# Current_Sense.net
KiCad netlist of a schematic drawn in Altium Designer
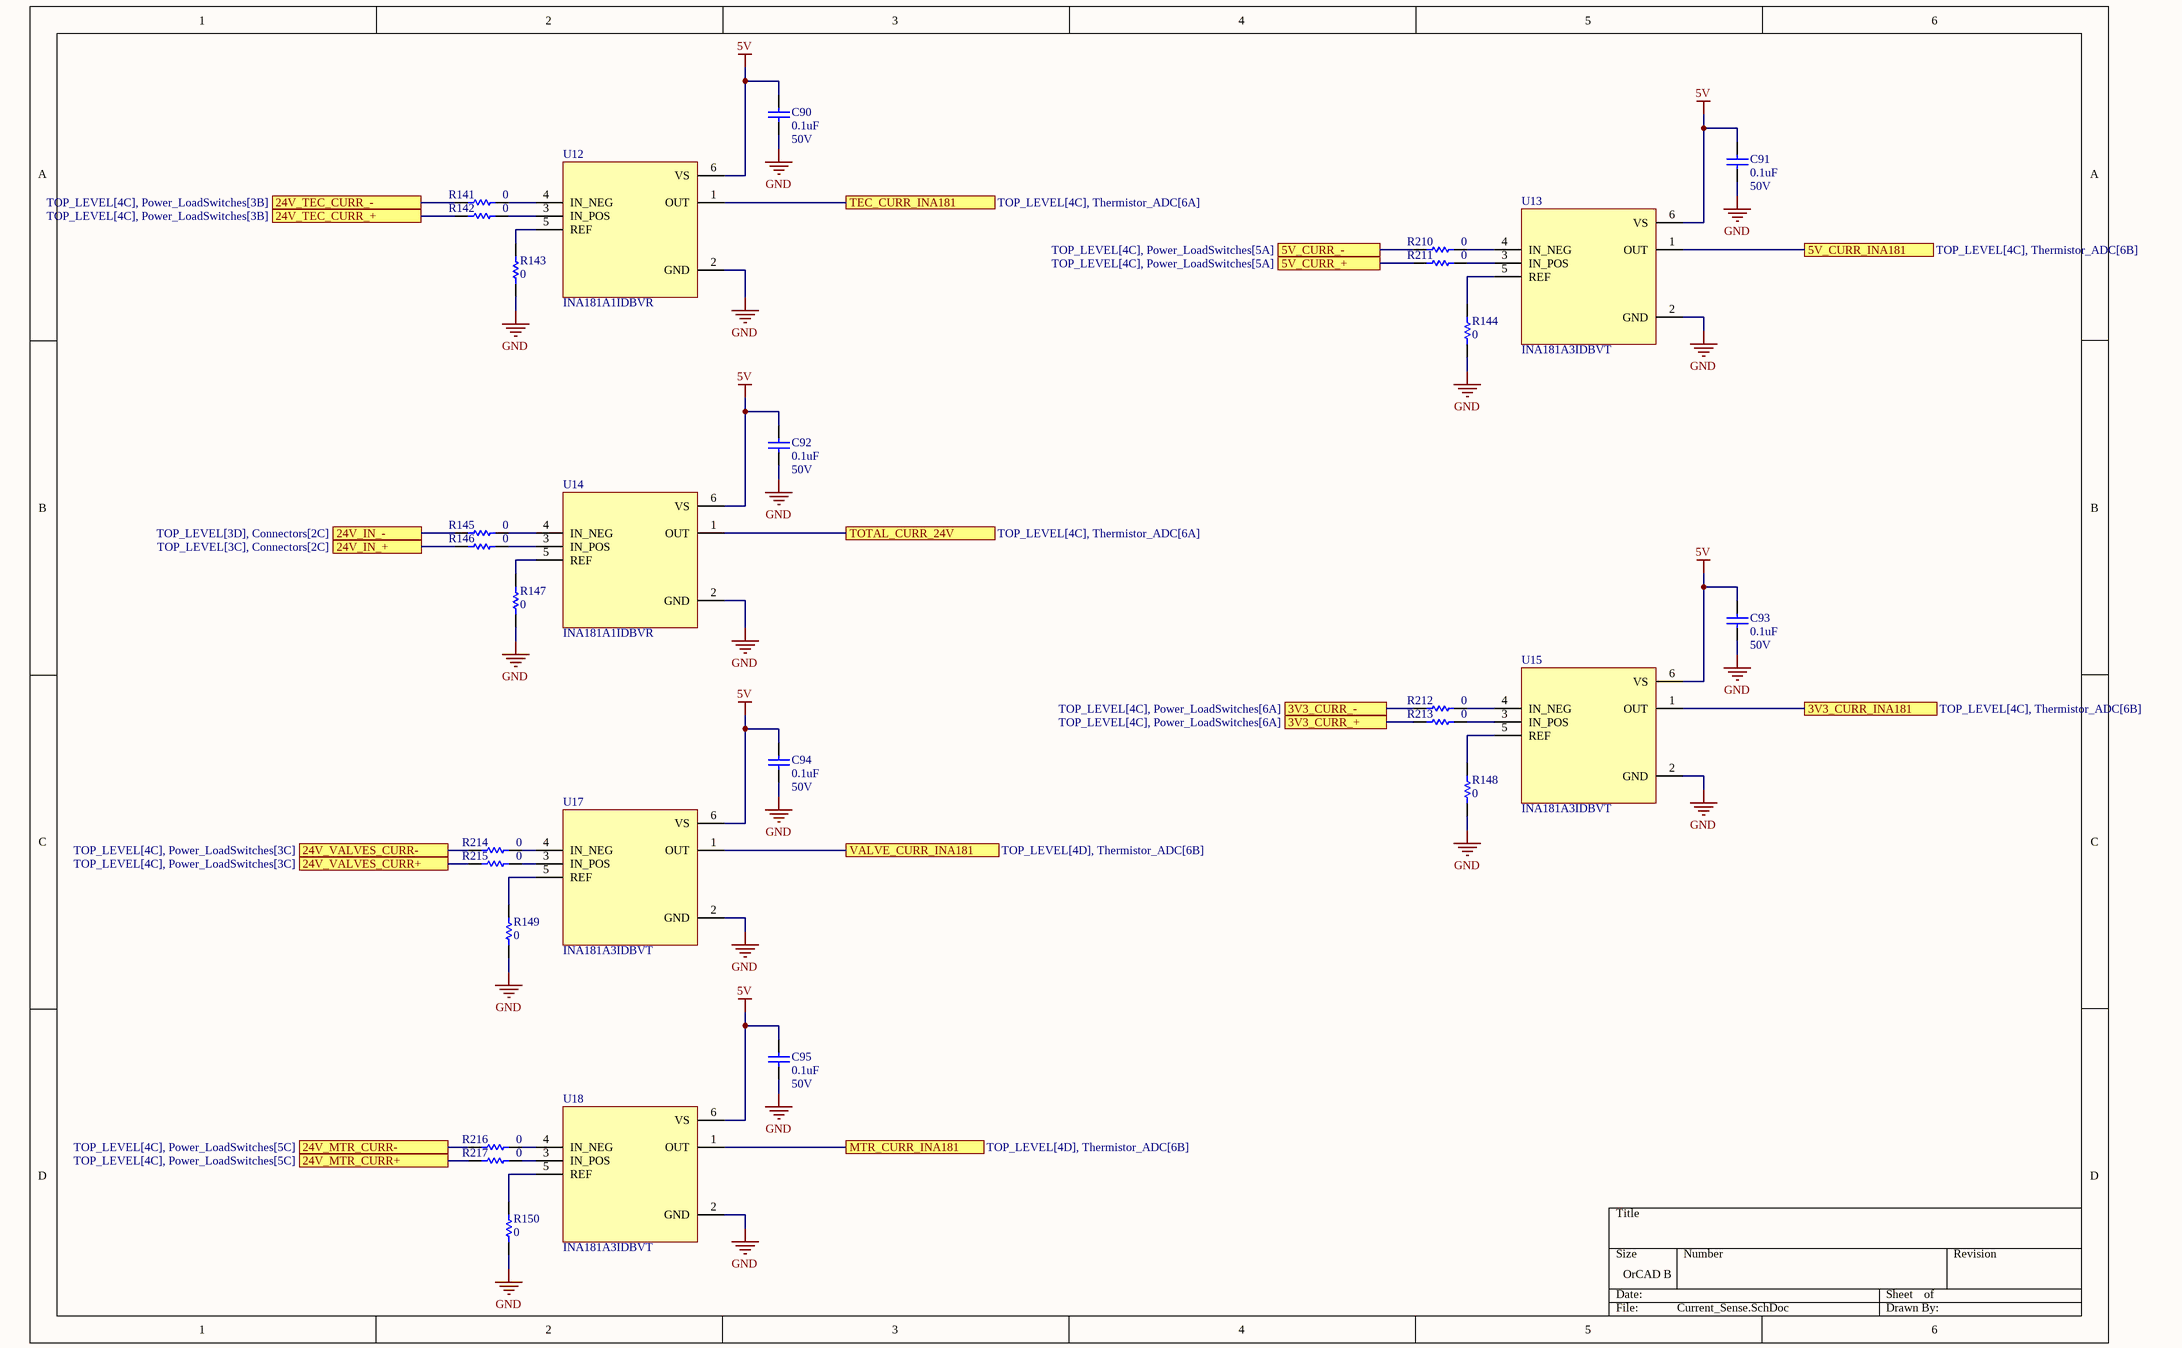
[diagram p0: Current_Sense.SchDoc]

(export (version "E")
  (design (tool "Eeschema 10.0.6"))
  (components
    (comp (ref "C90")
      (value "0.1uF")
      (footprint "DEFAULT_CAPACITOR_0805")
      (description "CAP CER 0.1UF 50V X7R 0805")
      (fields
        (field (name "MANUFACTURER") "Cal-Chip Electronics, Inc.")
        (field (name "RATING") "50V")
        (field (name "Comment") "KGM21NR71H104KT")
      )
      (libsource (lib "Avery Altium Llibrary") (part "KGM21NR71H104KT"))
    )
    (comp (ref "C91")
      (value "0.1uF")
      (footprint "DEFAULT_CAPACITOR_0805")
      (description "CAP CER 0.1UF 50V X7R 0805")
      (fields
        (field (name "MANUFACTURER") "Cal-Chip Electronics, Inc.")
        (field (name "RATING") "50V")
        (field (name "Comment") "KGM21NR71H104KT")
      )
      (libsource (lib "Avery Altium Llibrary") (part "KGM21NR71H104KT"))
    )
    (comp (ref "C92")
      (value "0.1uF")
      (footprint "DEFAULT_CAPACITOR_0805")
      (description "CAP CER 0.1UF 50V X7R 0805")
      (fields
        (field (name "MANUFACTURER") "Cal-Chip Electronics, Inc.")
        (field (name "RATING") "50V")
        (field (name "Comment") "KGM21NR71H104KT")
      )
      (libsource (lib "Avery Altium Llibrary") (part "KGM21NR71H104KT"))
    )
    (comp (ref "C93")
      (value "0.1uF")
      (footprint "DEFAULT_CAPACITOR_0805")
      (description "CAP CER 0.1UF 50V X7R 0805")
      (fields
        (field (name "MANUFACTURER") "Cal-Chip Electronics, Inc.")
        (field (name "RATING") "50V")
        (field (name "Comment") "KGM21NR71H104KT")
      )
      (libsource (lib "Avery Altium Llibrary") (part "KGM21NR71H104KT"))
    )
    (comp (ref "C94")
      (value "0.1uF")
      (footprint "DEFAULT_CAPACITOR_0805")
      (description "CAP CER 0.1UF 50V X7R 0805")
      (fields
        (field (name "MANUFACTURER") "Cal-Chip Electronics, Inc.")
        (field (name "RATING") "50V")
        (field (name "Comment") "KGM21NR71H104KT")
      )
      (libsource (lib "Avery Altium Llibrary") (part "KGM21NR71H104KT"))
    )
    (comp (ref "C95")
      (value "0.1uF")
      (footprint "DEFAULT_CAPACITOR_0805")
      (description "CAP CER 0.1UF 50V X7R 0805")
      (fields
        (field (name "MANUFACTURER") "Cal-Chip Electronics, Inc.")
        (field (name "RATING") "50V")
        (field (name "Comment") "KGM21NR71H104KT")
      )
      (libsource (lib "Avery Altium Llibrary") (part "KGM21NR71H104KT"))
    )
    (comp (ref "R141")
      (value "0")
      (footprint "DEFAULT_RESISTOR_0805")
      (description "RES 0 OHM JUMPER 1/8W 0805")
      (fields (field (name "POWER") "1/8W") (field (name "Comment") "RC0805JR-070RL"))
      (libsource (lib "Avery Altium Llibrary") (part "RC0805JR-070RL"))
    )
    (comp (ref "R142")
      (value "0")
      (footprint "DEFAULT_RESISTOR_0805")
      (description "RES 0 OHM JUMPER 1/8W 0805")
      (fields (field (name "POWER") "1/8W") (field (name "Comment") "RC0805JR-070RL"))
      (libsource (lib "Avery Altium Llibrary") (part "RC0805JR-070RL"))
    )
    (comp (ref "R143")
      (value "0")
      (footprint "DEFAULT_RESISTOR_0805")
      (description "RES 0 OHM JUMPER 1/8W 0805")
      (fields (field (name "POWER") "1/8W") (field (name "Comment") "RC0805JR-070RL"))
      (libsource (lib "Avery Altium Llibrary") (part "RC0805JR-070RL"))
    )
    (comp (ref "R144")
      (value "0")
      (footprint "DEFAULT_RESISTOR_0805")
      (description "RES 0 OHM JUMPER 1/8W 0805")
      (fields (field (name "POWER") "1/8W") (field (name "Comment") "RC0805JR-070RL"))
      (libsource (lib "Avery Altium Llibrary") (part "RC0805JR-070RL"))
    )
    (comp (ref "R145")
      (value "0")
      (footprint "DEFAULT_RESISTOR_0805")
      (description "RES 0 OHM JUMPER 1/8W 0805")
      (fields (field (name "POWER") "1/8W") (field (name "Comment") "RC0805JR-070RL"))
      (libsource (lib "Avery Altium Llibrary") (part "RC0805JR-070RL"))
    )
    (comp (ref "R146")
      (value "0")
      (footprint "DEFAULT_RESISTOR_0805")
      (description "RES 0 OHM JUMPER 1/8W 0805")
      (fields (field (name "POWER") "1/8W") (field (name "Comment") "RC0805JR-070RL"))
      (libsource (lib "Avery Altium Llibrary") (part "RC0805JR-070RL"))
    )
    (comp (ref "R147")
      (value "0")
      (footprint "DEFAULT_RESISTOR_0805")
      (description "RES 0 OHM JUMPER 1/8W 0805")
      (fields (field (name "POWER") "1/8W") (field (name "Comment") "RC0805JR-070RL"))
      (libsource (lib "Avery Altium Llibrary") (part "RC0805JR-070RL"))
    )
    (comp (ref "R148")
      (value "0")
      (footprint "DEFAULT_RESISTOR_0805")
      (description "RES 0 OHM JUMPER 1/8W 0805")
      (fields (field (name "POWER") "1/8W") (field (name "Comment") "RC0805JR-070RL"))
      (libsource (lib "Avery Altium Llibrary") (part "RC0805JR-070RL"))
    )
    (comp (ref "R149")
      (value "0")
      (footprint "DEFAULT_RESISTOR_0805")
      (description "RES 0 OHM JUMPER 1/8W 0805")
      (fields (field (name "POWER") "1/8W") (field (name "Comment") "RC0805JR-070RL"))
      (libsource (lib "Avery Altium Llibrary") (part "RC0805JR-070RL"))
    )
    (comp (ref "R150")
      (value "0")
      (footprint "DEFAULT_RESISTOR_0805")
      (description "RES 0 OHM JUMPER 1/8W 0805")
      (fields (field (name "POWER") "1/8W") (field (name "Comment") "RC0805JR-070RL"))
      (libsource (lib "Avery Altium Llibrary") (part "RC0805JR-070RL"))
    )
    (comp (ref "R210")
      (value "0")
      (footprint "DEFAULT_RESISTOR_0805")
      (description "RES 0 OHM JUMPER 1/8W 0805")
      (fields (field (name "POWER") "1/8W") (field (name "Comment") "RC0805JR-070RL"))
      (libsource (lib "Avery Altium Llibrary") (part "RC0805JR-070RL"))
    )
    (comp (ref "R211")
      (value "0")
      (footprint "DEFAULT_RESISTOR_0805")
      (description "RES 0 OHM JUMPER 1/8W 0805")
      (fields (field (name "POWER") "1/8W") (field (name "Comment") "RC0805JR-070RL"))
      (libsource (lib "Avery Altium Llibrary") (part "RC0805JR-070RL"))
    )
    (comp (ref "R212")
      (value "0")
      (footprint "DEFAULT_RESISTOR_0805")
      (description "RES 0 OHM JUMPER 1/8W 0805")
      (fields (field (name "POWER") "1/8W") (field (name "Comment") "RC0805JR-070RL"))
      (libsource (lib "Avery Altium Llibrary") (part "RC0805JR-070RL"))
    )
    (comp (ref "R213")
      (value "0")
      (footprint "DEFAULT_RESISTOR_0805")
      (description "RES 0 OHM JUMPER 1/8W 0805")
      (fields (field (name "POWER") "1/8W") (field (name "Comment") "RC0805JR-070RL"))
      (libsource (lib "Avery Altium Llibrary") (part "RC0805JR-070RL"))
    )
    (comp (ref "R214")
      (value "0")
      (footprint "DEFAULT_RESISTOR_0805")
      (description "RES 0 OHM JUMPER 1/8W 0805")
      (fields (field (name "POWER") "1/8W") (field (name "Comment") "RC0805JR-070RL"))
      (libsource (lib "Avery Altium Llibrary") (part "RC0805JR-070RL"))
    )
    (comp (ref "R215")
      (value "0")
      (footprint "DEFAULT_RESISTOR_0805")
      (description "RES 0 OHM JUMPER 1/8W 0805")
      (fields (field (name "POWER") "1/8W") (field (name "Comment") "RC0805JR-070RL"))
      (libsource (lib "Avery Altium Llibrary") (part "RC0805JR-070RL"))
    )
    (comp (ref "R216")
      (value "0")
      (footprint "DEFAULT_RESISTOR_0805")
      (description "RES 0 OHM JUMPER 1/8W 0805")
      (fields (field (name "POWER") "1/8W") (field (name "Comment") "RC0805JR-070RL"))
      (libsource (lib "Avery Altium Llibrary") (part "RC0805JR-070RL"))
    )
    (comp (ref "R217")
      (value "0")
      (footprint "DEFAULT_RESISTOR_0805")
      (description "RES 0 OHM JUMPER 1/8W 0805")
      (fields (field (name "POWER") "1/8W") (field (name "Comment") "RC0805JR-070RL"))
      (libsource (lib "Avery Altium Llibrary") (part "RC0805JR-070RL"))
    )
    (comp (ref "U12")
      (value "INA181A1IDBVR")
      (footprint "INA181A1IDBVR")
      (description "IC CURR SENSE 1 CIRCUIT SOT23-6")
      (fields (field (name "MF") "Texas Instruments"))
      (libsource (lib "Avery Schem Library") (part "INA181A1IDBVR"))
    )
    (comp (ref "U13")
      (value "INA181A3IDBVT")
      (footprint "INA181A1IDBVR")
      (description "IC CURR SENSE 1 CIRCUIT SOT23-6")
      (fields (field (name "MF") "Texas Instruments") (field (name "MP") "INA181A1IDBVR"))
      (libsource (lib "Avery Schem Library") (part "INA181A3IDBVT"))
    )
    (comp (ref "U14")
      (value "INA181A1IDBVR")
      (footprint "INA181A1IDBVR")
      (description "IC CURR SENSE 1 CIRCUIT SOT23-6")
      (fields (field (name "MF") "Texas Instruments"))
      (libsource (lib "Avery Schem Library") (part "INA181A1IDBVR"))
    )
    (comp (ref "U15")
      (value "INA181A3IDBVT")
      (footprint "INA181A1IDBVR")
      (description "IC CURR SENSE 1 CIRCUIT SOT23-6")
      (fields (field (name "MF") "Texas Instruments") (field (name "MP") "INA181A1IDBVR"))
      (libsource (lib "Avery Schem Library") (part "INA181A3IDBVT"))
    )
    (comp (ref "U17")
      (value "INA181A3IDBVT")
      (footprint "INA181A1IDBVR")
      (description "IC CURR SENSE 1 CIRCUIT SOT23-6")
      (fields (field (name "MF") "Texas Instruments") (field (name "MP") "INA181A1IDBVR"))
      (libsource (lib "Avery Schem Library") (part "INA181A3IDBVT"))
    )
    (comp (ref "U18")
      (value "INA181A3IDBVT")
      (footprint "INA181A1IDBVR")
      (description "IC CURR SENSE 1 CIRCUIT SOT23-6")
      (fields (field (name "MF") "Texas Instruments") (field (name "MP") "INA181A1IDBVR"))
      (libsource (lib "Avery Schem Library") (part "INA181A3IDBVT"))
    )
  )
  (nets
    (net (code "1") (name "/3V3_CURR_+") (class "Default")
      (node (ref "R213") (pin "2") (pinfunction "2_2") (pintype "passive"))
    )
    (net (code "2") (name "/3V3_CURR_-") (class "Default")
      (node (ref "R212") (pin "2") (pinfunction "2_2") (pintype "passive"))
    )
    (net (code "3") (name "/3V3_CURR_INA181") (class "Default")
      (node (ref "U15") (pin "1") (pinfunction "OUT_1") (pintype "passive"))
    )
    (net (code "4") (name "/5V_CURR_+") (class "Default")
      (node (ref "R211") (pin "2") (pinfunction "2_2") (pintype "passive"))
    )
    (net (code "5") (name "/5V_CURR_-") (class "Default")
      (node (ref "R210") (pin "2") (pinfunction "2_2") (pintype "passive"))
    )
    (net (code "6") (name "/5V_CURR_INA181") (class "Default")
      (node (ref "U13") (pin "1") (pinfunction "OUT_1") (pintype "passive"))
    )
    (net (code "7") (name "/24V_IN_+") (class "Default")
      (node (ref "R146") (pin "2") (pinfunction "2_2") (pintype "passive"))
    )
    (net (code "8") (name "/24V_IN_-") (class "Default")
      (node (ref "R145") (pin "2") (pinfunction "2_2") (pintype "passive"))
    )
    (net (code "9") (name "/24V_MTR_CURR+") (class "Default")
      (node (ref "R217") (pin "2") (pinfunction "2_2") (pintype "passive"))
    )
    (net (code "10") (name "/24V_MTR_CURR-") (class "Default")
      (node (ref "R216") (pin "2") (pinfunction "2_2") (pintype "passive"))
    )
    (net (code "11") (name "/24V_TEC_CURR_+") (class "Default")
      (node (ref "R142") (pin "2") (pinfunction "2_2") (pintype "passive"))
    )
    (net (code "12") (name "/24V_TEC_CURR_-") (class "Default")
      (node (ref "R141") (pin "2") (pinfunction "2_2") (pintype "passive"))
    )
    (net (code "13") (name "/24V_VALVES_CURR+") (class "Default")
      (node (ref "R215") (pin "2") (pinfunction "2_2") (pintype "passive"))
    )
    (net (code "14") (name "/24V_VALVES_CURR-") (class "Default")
      (node (ref "R214") (pin "2") (pinfunction "2_2") (pintype "passive"))
    )
    (net (code "15") (name "/MTR_CURR_INA181") (class "Default")
      (node (ref "U18") (pin "1") (pinfunction "OUT_1") (pintype "passive"))
    )
    (net (code "16") (name "/TEC_CURR_INA181") (class "Default")
      (node (ref "U12") (pin "1") (pinfunction "OUT_1") (pintype "passive"))
    )
    (net (code "17") (name "/TOTAL_CURR_24V") (class "Default")
      (node (ref "U14") (pin "1") (pinfunction "OUT_1") (pintype "passive"))
    )
    (net (code "18") (name "/VALVE_CURR_INA181") (class "Default")
      (node (ref "U17") (pin "1") (pinfunction "OUT_1") (pintype "passive"))
    )
    (net (code "19") (name "5V") (class "Default")
      (node (ref "C90") (pin "2") (pinfunction "2_2") (pintype "passive"))
      (node (ref "C91") (pin "2") (pinfunction "2_2") (pintype "passive"))
      (node (ref "C92") (pin "2") (pinfunction "2_2") (pintype "passive"))
      (node (ref "C93") (pin "2") (pinfunction "2_2") (pintype "passive"))
      (node (ref "C94") (pin "2") (pinfunction "2_2") (pintype "passive"))
      (node (ref "C95") (pin "2") (pinfunction "2_2") (pintype "passive"))
      (node (ref "U12") (pin "6") (pinfunction "VS_6") (pintype "power_in"))
      (node (ref "U13") (pin "6") (pinfunction "VS_6") (pintype "power_in"))
      (node (ref "U14") (pin "6") (pinfunction "VS_6") (pintype "power_in"))
      (node (ref "U15") (pin "6") (pinfunction "VS_6") (pintype "power_in"))
      (node (ref "U17") (pin "6") (pinfunction "VS_6") (pintype "power_in"))
      (node (ref "U18") (pin "6") (pinfunction "VS_6") (pintype "power_in"))
    )
    (net (code "20") (name "GND") (class "Default")
      (node (ref "C90") (pin "1") (pinfunction "1_1") (pintype "passive"))
      (node (ref "C91") (pin "1") (pinfunction "1_1") (pintype "passive"))
      (node (ref "C92") (pin "1") (pinfunction "1_1") (pintype "passive"))
      (node (ref "C93") (pin "1") (pinfunction "1_1") (pintype "passive"))
      (node (ref "C94") (pin "1") (pinfunction "1_1") (pintype "passive"))
      (node (ref "C95") (pin "1") (pinfunction "1_1") (pintype "passive"))
      (node (ref "R143") (pin "2") (pinfunction "2_2") (pintype "passive"))
      (node (ref "R144") (pin "2") (pinfunction "2_2") (pintype "passive"))
      (node (ref "R147") (pin "2") (pinfunction "2_2") (pintype "passive"))
      (node (ref "R148") (pin "2") (pinfunction "2_2") (pintype "passive"))
      (node (ref "R149") (pin "2") (pinfunction "2_2") (pintype "passive"))
      (node (ref "R150") (pin "2") (pinfunction "2_2") (pintype "passive"))
      (node (ref "U12") (pin "2") (pinfunction "GND_2") (pintype "power_in"))
      (node (ref "U13") (pin "2") (pinfunction "GND_2") (pintype "power_in"))
      (node (ref "U14") (pin "2") (pinfunction "GND_2") (pintype "power_in"))
      (node (ref "U15") (pin "2") (pinfunction "GND_2") (pintype "power_in"))
      (node (ref "U17") (pin "2") (pinfunction "GND_2") (pintype "power_in"))
      (node (ref "U18") (pin "2") (pinfunction "GND_2") (pintype "power_in"))
    )
    (net (code "21") (name "Net-(U12-IN_NEG)") (class "Default")
      (node (ref "R141") (pin "1") (pinfunction "1_1") (pintype "passive"))
      (node (ref "U12") (pin "4") (pinfunction "IN_NEG_4") (pintype "passive"))
    )
    (net (code "22") (name "Net-(U12-IN_POS)") (class "Default")
      (node (ref "R142") (pin "1") (pinfunction "1_1") (pintype "passive"))
      (node (ref "U12") (pin "3") (pinfunction "IN_POS_3") (pintype "passive"))
    )
    (net (code "23") (name "Net-(U12-REF)") (class "Default")
      (node (ref "R143") (pin "1") (pinfunction "1_1") (pintype "passive"))
      (node (ref "U12") (pin "5") (pinfunction "REF_5") (pintype "passive"))
    )
    (net (code "24") (name "Net-(U13-IN_NEG)") (class "Default")
      (node (ref "R210") (pin "1") (pinfunction "1_1") (pintype "passive"))
      (node (ref "U13") (pin "4") (pinfunction "IN_NEG_4") (pintype "passive"))
    )
    (net (code "25") (name "Net-(U13-IN_POS)") (class "Default")
      (node (ref "R211") (pin "1") (pinfunction "1_1") (pintype "passive"))
      (node (ref "U13") (pin "3") (pinfunction "IN_POS_3") (pintype "passive"))
    )
    (net (code "26") (name "Net-(U13-REF)") (class "Default")
      (node (ref "R144") (pin "1") (pinfunction "1_1") (pintype "passive"))
      (node (ref "U13") (pin "5") (pinfunction "REF_5") (pintype "passive"))
    )
    (net (code "27") (name "Net-(U14-IN_NEG)") (class "Default")
      (node (ref "R145") (pin "1") (pinfunction "1_1") (pintype "passive"))
      (node (ref "U14") (pin "4") (pinfunction "IN_NEG_4") (pintype "passive"))
    )
    (net (code "28") (name "Net-(U14-IN_POS)") (class "Default")
      (node (ref "R146") (pin "1") (pinfunction "1_1") (pintype "passive"))
      (node (ref "U14") (pin "3") (pinfunction "IN_POS_3") (pintype "passive"))
    )
    (net (code "29") (name "Net-(U14-REF)") (class "Default")
      (node (ref "R147") (pin "1") (pinfunction "1_1") (pintype "passive"))
      (node (ref "U14") (pin "5") (pinfunction "REF_5") (pintype "passive"))
    )
    (net (code "30") (name "Net-(U15-IN_NEG)") (class "Default")
      (node (ref "R212") (pin "1") (pinfunction "1_1") (pintype "passive"))
      (node (ref "U15") (pin "4") (pinfunction "IN_NEG_4") (pintype "passive"))
    )
    (net (code "31") (name "Net-(U15-IN_POS)") (class "Default")
      (node (ref "R213") (pin "1") (pinfunction "1_1") (pintype "passive"))
      (node (ref "U15") (pin "3") (pinfunction "IN_POS_3") (pintype "passive"))
    )
    (net (code "32") (name "Net-(U15-REF)") (class "Default")
      (node (ref "R148") (pin "1") (pinfunction "1_1") (pintype "passive"))
      (node (ref "U15") (pin "5") (pinfunction "REF_5") (pintype "passive"))
    )
    (net (code "33") (name "Net-(U17-IN_NEG)") (class "Default")
      (node (ref "R214") (pin "1") (pinfunction "1_1") (pintype "passive"))
      (node (ref "U17") (pin "4") (pinfunction "IN_NEG_4") (pintype "passive"))
    )
    (net (code "34") (name "Net-(U17-IN_POS)") (class "Default")
      (node (ref "R215") (pin "1") (pinfunction "1_1") (pintype "passive"))
      (node (ref "U17") (pin "3") (pinfunction "IN_POS_3") (pintype "passive"))
    )
    (net (code "35") (name "Net-(U17-REF)") (class "Default")
      (node (ref "R149") (pin "1") (pinfunction "1_1") (pintype "passive"))
      (node (ref "U17") (pin "5") (pinfunction "REF_5") (pintype "passive"))
    )
    (net (code "36") (name "Net-(U18-IN_NEG)") (class "Default")
      (node (ref "R216") (pin "1") (pinfunction "1_1") (pintype "passive"))
      (node (ref "U18") (pin "4") (pinfunction "IN_NEG_4") (pintype "passive"))
    )
    (net (code "37") (name "Net-(U18-IN_POS)") (class "Default")
      (node (ref "R217") (pin "1") (pinfunction "1_1") (pintype "passive"))
      (node (ref "U18") (pin "3") (pinfunction "IN_POS_3") (pintype "passive"))
    )
    (net (code "38") (name "Net-(U18-REF)") (class "Default")
      (node (ref "R150") (pin "1") (pinfunction "1_1") (pintype "passive"))
      (node (ref "U18") (pin "5") (pinfunction "REF_5") (pintype "passive"))
    )
  )
)
